# Funkboard_v3.net
KiCad netlist of a schematic drawn in EAGLE
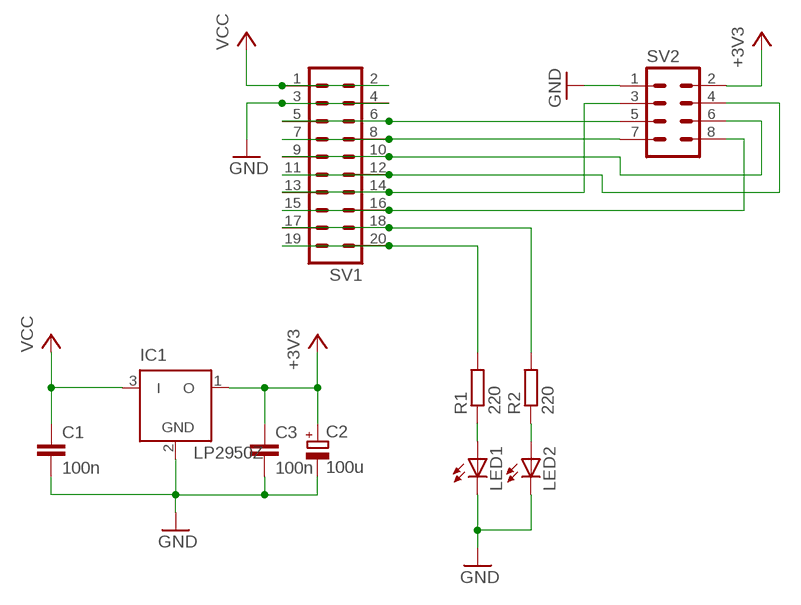
[diagram p0: schematic, sheet 1]

(export (version "E")
  (design (tool "Eeschema 10.0.6"))
  (components
    (comp (ref "C1")
      (value "100n")
      (footprint "eagle-import:C025-025X050")
      (libsource (lib "eagle-import") (part "C-EU025-025X050"))
    )
    (comp (ref "C2")
      (value "100u")
      (footprint "eagle-import:E2,5-6")
      (libsource (lib "eagle-import") (part "CPOL-EUE2.5-6"))
    )
    (comp (ref "C3")
      (value "100n")
      (footprint "eagle-import:C025-025X050")
      (libsource (lib "eagle-import") (part "C-EU025-025X050"))
    )
    (comp (ref "IC1")
      (value "LP2950Z")
      (footprint "eagle-import:TO92")
      (libsource (lib "eagle-import") (part "LP2950Z"))
    )
    (comp (ref "LED1")
      (value "LED3MM")
      (footprint "eagle-import:LED3MM")
      (libsource (lib "eagle-import") (part "LED3MM"))
    )
    (comp (ref "LED2")
      (value "LED3MM")
      (footprint "eagle-import:LED3MM")
      (libsource (lib "eagle-import") (part "LED3MM"))
    )
    (comp (ref "R1")
      (value "220")
      (footprint "eagle-import:0204_7")
      (libsource (lib "eagle-import") (part "R-EU_0204/7"))
    )
    (comp (ref "R2")
      (value "220")
      (footprint "eagle-import:0204_7")
      (libsource (lib "eagle-import") (part "R-EU_0204/7"))
    )
    (comp (ref "SV1")
      (value "MA10-2W")
      (footprint "eagle-import:MA10-2W")
      (libsource (lib "eagle-import") (part "MA10-2W"))
    )
    (comp (ref "SV2")
      (value "MA04-2")
      (footprint "eagle-import:MA04-2")
      (libsource (lib "eagle-import") (part "MA04-2"))
    )
  )
  (nets
    (net (code "1") (name "+3V3") (class "Default")
      (node (ref "C2") (pin "+") (pinfunction "+_+") (pintype "passive"))
      (node (ref "C3") (pin "1") (pinfunction "1_1") (pintype "passive"))
      (node (ref "IC1") (pin "1") (pinfunction "O_1") (pintype "input"))
      (node (ref "SV2") (pin "2") (pinfunction "2_2") (pintype "passive"))
    )
    (net (code "2") (name "GND") (class "Default")
      (node (ref "C1") (pin "2") (pinfunction "2_2") (pintype "passive"))
      (node (ref "C2") (pin "-") (pinfunction "-_-") (pintype "passive"))
      (node (ref "C3") (pin "2") (pinfunction "2_2") (pintype "passive"))
      (node (ref "IC1") (pin "2") (pinfunction "GND_2") (pintype "power_in"))
      (node (ref "LED1") (pin "K") (pinfunction "C_K") (pintype "passive"))
      (node (ref "LED2") (pin "K") (pinfunction "C_K") (pintype "passive"))
      (node (ref "SV1") (pin "3") (pinfunction "3_3") (pintype "passive"))
      (node (ref "SV1") (pin "4") (pinfunction "4_4") (pintype "passive"))
      (node (ref "SV2") (pin "1") (pinfunction "1_1") (pintype "passive"))
    )
    (net (code "3") (name "Net-(LED1-PadA)") (class "Default")
      (node (ref "LED1") (pin "A") (pinfunction "A_A") (pintype "passive"))
      (node (ref "R1") (pin "1") (pinfunction "1_1") (pintype "passive"))
    )
    (net (code "4") (name "Net-(LED2-PadA)") (class "Default")
      (node (ref "LED2") (pin "A") (pinfunction "A_A") (pintype "passive"))
      (node (ref "R2") (pin "1") (pinfunction "1_1") (pintype "passive"))
    )
    (net (code "5") (name "Net-(R1-Pad2)") (class "Default")
      (node (ref "R1") (pin "2") (pinfunction "2_2") (pintype "passive"))
      (node (ref "SV1") (pin "19") (pinfunction "19_19") (pintype "passive"))
      (node (ref "SV1") (pin "20") (pinfunction "20_20") (pintype "passive"))
    )
    (net (code "6") (name "Net-(R2-Pad2)") (class "Default")
      (node (ref "R2") (pin "2") (pinfunction "2_2") (pintype "passive"))
      (node (ref "SV1") (pin "17") (pinfunction "17_17") (pintype "passive"))
      (node (ref "SV1") (pin "18") (pinfunction "18_18") (pintype "passive"))
    )
    (net (code "7") (name "Net-(SV1-Pad5)") (class "Default")
      (node (ref "SV1") (pin "5") (pinfunction "5_5") (pintype "passive"))
      (node (ref "SV1") (pin "6") (pinfunction "6_6") (pintype "passive"))
      (node (ref "SV2") (pin "5") (pinfunction "5_5") (pintype "passive"))
    )
    (net (code "8") (name "Net-(SV1-Pad7)") (class "Default")
      (node (ref "SV1") (pin "7") (pinfunction "7_7") (pintype "passive"))
      (node (ref "SV1") (pin "8") (pinfunction "8_8") (pintype "passive"))
      (node (ref "SV2") (pin "7") (pinfunction "7_7") (pintype "passive"))
    )
    (net (code "9") (name "Net-(SV1-Pad10)") (class "Default")
      (node (ref "SV1") (pin "10") (pinfunction "10_10") (pintype "passive"))
      (node (ref "SV1") (pin "9") (pinfunction "9_9") (pintype "passive"))
      (node (ref "SV2") (pin "6") (pinfunction "6_6") (pintype "passive"))
    )
    (net (code "10") (name "Net-(SV1-Pad11)") (class "Default")
      (node (ref "SV1") (pin "11") (pinfunction "11_11") (pintype "passive"))
      (node (ref "SV1") (pin "12") (pinfunction "12_12") (pintype "passive"))
      (node (ref "SV2") (pin "4") (pinfunction "4_4") (pintype "passive"))
    )
    (net (code "11") (name "Net-(SV1-Pad13)") (class "Default")
      (node (ref "SV1") (pin "13") (pinfunction "13_13") (pintype "passive"))
      (node (ref "SV1") (pin "14") (pinfunction "14_14") (pintype "passive"))
      (node (ref "SV2") (pin "3") (pinfunction "3_3") (pintype "passive"))
    )
    (net (code "12") (name "Net-(SV1-Pad15)") (class "Default")
      (node (ref "SV1") (pin "15") (pinfunction "15_15") (pintype "passive"))
      (node (ref "SV1") (pin "16") (pinfunction "16_16") (pintype "passive"))
      (node (ref "SV2") (pin "8") (pinfunction "8_8") (pintype "passive"))
    )
    (net (code "13") (name "VCC") (class "Default")
      (node (ref "C1") (pin "1") (pinfunction "1_1") (pintype "passive"))
      (node (ref "IC1") (pin "3") (pinfunction "I_3") (pintype "input"))
      (node (ref "SV1") (pin "1") (pinfunction "1_1") (pintype "passive"))
      (node (ref "SV1") (pin "2") (pinfunction "2_2") (pintype "passive"))
    )
  )
)
